# Projet_4A_Arrosage_Automatique1.net
KiCad netlist of a schematic drawn in EAGLE
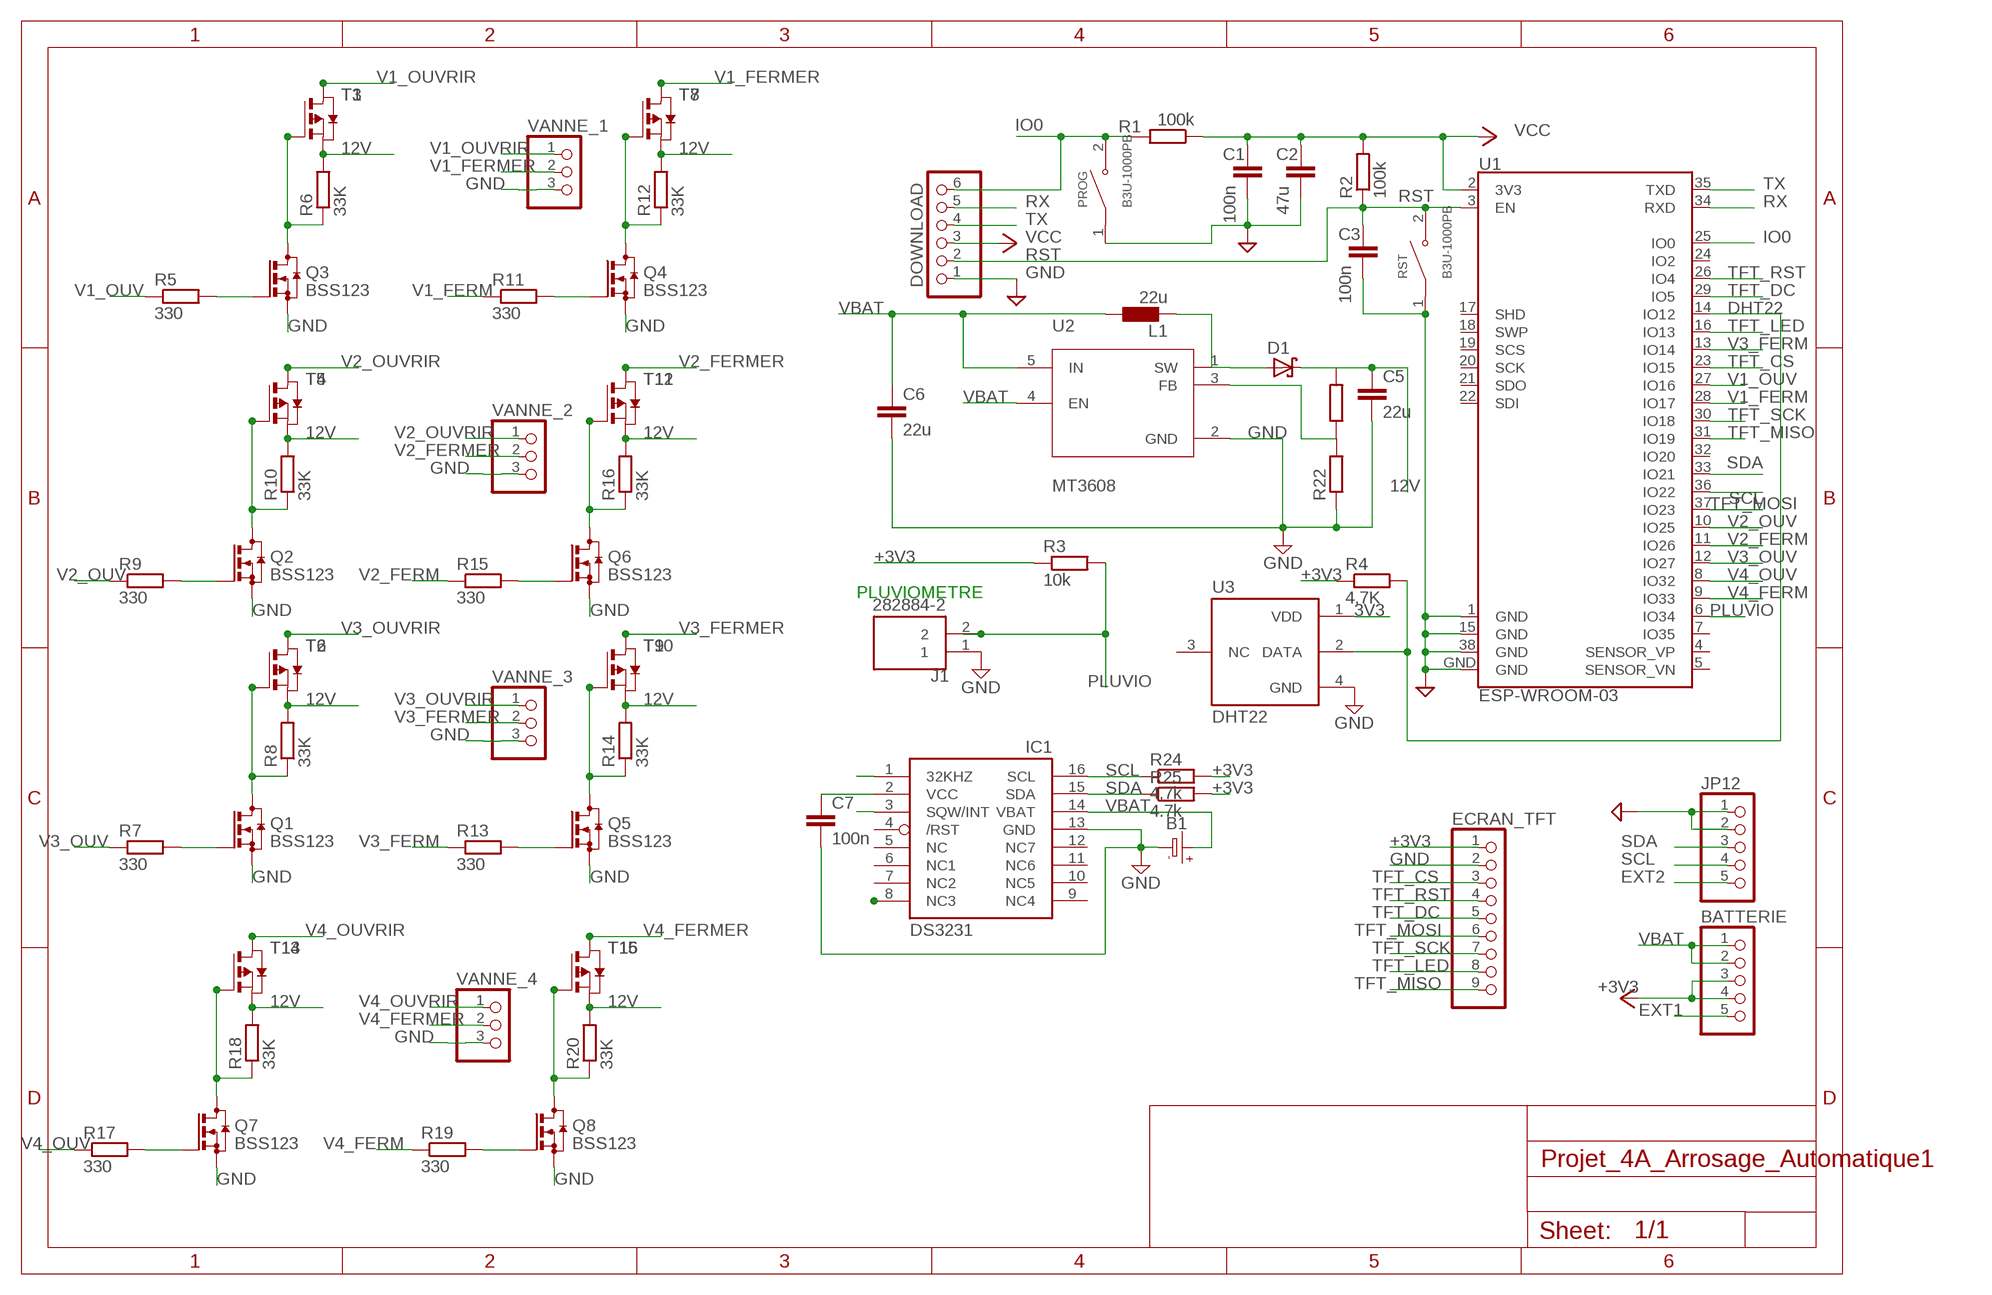
[diagram p0: schematic, sheet 1]

(export (version "E")
  (design (tool "Eeschema 10.0.6"))
  (components
    (comp (ref "B1")
      (value "BATTERYCR2032_BAT-HLD-001")
      (footprint "eagle-import:CR2032_SMT_BAT-HLD-001")
      (libsource (lib "eagle-import") (part "BATTERYCR2032_BAT-HLD-001"))
    )
    (comp (ref "BATTERIE")
      (value "PINHD-1X5S")
      (footprint "eagle-import:1X05S")
      (libsource (lib "eagle-import") (part "PINHD-1X5S"))
    )
    (comp (ref "C1")
      (value "100n")
      (footprint "eagle-import:C0805")
      (libsource (lib "eagle-import") (part "C"))
    )
    (comp (ref "C2")
      (value "47u")
      (footprint "eagle-import:C0805")
      (libsource (lib "eagle-import") (part "C"))
    )
    (comp (ref "C3")
      (value "100n")
      (footprint "eagle-import:C0805")
      (libsource (lib "eagle-import") (part "C"))
    )
    (comp (ref "C5")
      (value "22u")
      (footprint "eagle-import:C0805")
      (libsource (lib "eagle-import") (part "C"))
    )
    (comp (ref "C6")
      (value "22u")
      (footprint "eagle-import:C0805")
      (libsource (lib "eagle-import") (part "C"))
    )
    (comp (ref "C7")
      (value "100n")
      (footprint "eagle-import:C0805")
      (libsource (lib "eagle-import") (part "C"))
    )
    (comp (ref "D1")
      (value "SCHOTTKY-DIODEAG")
      (footprint "eagle-import:AG")
      (libsource (lib "eagle-import") (part "SCHOTTKY-DIODEAG"))
    )
    (comp (ref "DOWNLOAD")
      (value "PINHD-1X6S")
      (footprint "eagle-import:1X06S")
      (libsource (lib "eagle-import") (part "PINHD-1X6S"))
    )
    (comp (ref "ECRAN_TFT")
      (value "PINHD-1X9")
      (footprint "eagle-import:1X09")
      (libsource (lib "eagle-import") (part "PINHD-1X9"))
    )
    (comp (ref "IC1")
      (value "DS3231/SO")
      (footprint "eagle-import:SO16W")
      (fields (field (name "MF") "Analog Devices") (field (name "MP") "DS3231"))
      (libsource (lib "eagle-import") (part "DS3231/SO"))
    )
    (comp (ref "J1")
      (value "282884-2")
      (footprint "eagle-import:TE_282884-2")
      (fields (field (name "MF") "TE Connectivity"))
      (libsource (lib "eagle-import") (part "282884-2"))
    )
    (comp (ref "JP12")
      (value "PINHD-1X5S")
      (footprint "eagle-import:1X05S")
      (libsource (lib "eagle-import") (part "PINHD-1X5S"))
    )
    (comp (ref "L1")
      (value "22u")
      (footprint "eagle-import:0204_7")
      (libsource (lib "eagle-import") (part "L0204/7"))
    )
    (comp (ref "PROG")
      (value "B3U-1000PB")
      (footprint "eagle-import:SW_B3U-1000PB")
      (libsource (lib "eagle-import") (part "B3U-1000PB"))
    )
    (comp (ref "Q1")
      (value "BSS123")
      (footprint "eagle-import:SOT23")
      (libsource (lib "eagle-import") (part "BSS123"))
    )
    (comp (ref "Q2")
      (value "BSS123")
      (footprint "eagle-import:SOT23")
      (libsource (lib "eagle-import") (part "BSS123"))
    )
    (comp (ref "Q3")
      (value "BSS123")
      (footprint "eagle-import:SOT23")
      (libsource (lib "eagle-import") (part "BSS123"))
    )
    (comp (ref "Q4")
      (value "BSS123")
      (footprint "eagle-import:SOT23")
      (libsource (lib "eagle-import") (part "BSS123"))
    )
    (comp (ref "Q5")
      (value "BSS123")
      (footprint "eagle-import:SOT23")
      (libsource (lib "eagle-import") (part "BSS123"))
    )
    (comp (ref "Q6")
      (value "BSS123")
      (footprint "eagle-import:SOT23")
      (libsource (lib "eagle-import") (part "BSS123"))
    )
    (comp (ref "Q7")
      (value "BSS123")
      (footprint "eagle-import:SOT23")
      (libsource (lib "eagle-import") (part "BSS123"))
    )
    (comp (ref "Q8")
      (value "BSS123")
      (footprint "eagle-import:SOT23")
      (libsource (lib "eagle-import") (part "BSS123"))
    )
    (comp (ref "R1")
      (value "100k")
      (footprint "eagle-import:R1206")
      (libsource (lib "eagle-import") (part "RR1206"))
    )
    (comp (ref "R2")
      (value "100k")
      (footprint "eagle-import:R1206")
      (libsource (lib "eagle-import") (part "RR1206"))
    )
    (comp (ref "R3")
      (value "10k")
      (footprint "eagle-import:R0805")
      (libsource (lib "eagle-import") (part "R-EU_R0805"))
    )
    (comp (ref "R4")
      (value "4,7K")
      (footprint "eagle-import:0207_10")
      (libsource (lib "eagle-import") (part "R-EU_0207/10"))
    )
    (comp (ref "R5")
      (value "330")
      (footprint "eagle-import:0207_10")
      (libsource (lib "eagle-import") (part "R-EU_0207/10"))
    )
    (comp (ref "R6")
      (value "33K")
      (footprint "eagle-import:0207_10")
      (libsource (lib "eagle-import") (part "R-EU_0207/10"))
    )
    (comp (ref "R7")
      (value "330")
      (footprint "eagle-import:0207_10")
      (libsource (lib "eagle-import") (part "R-EU_0207/10"))
    )
    (comp (ref "R8")
      (value "33K")
      (footprint "eagle-import:0207_10")
      (libsource (lib "eagle-import") (part "R-EU_0207/10"))
    )
    (comp (ref "R9")
      (value "330")
      (footprint "eagle-import:0207_10")
      (libsource (lib "eagle-import") (part "R-EU_0207/10"))
    )
    (comp (ref "R10")
      (value "33K")
      (footprint "eagle-import:0207_10")
      (libsource (lib "eagle-import") (part "R-EU_0207/10"))
    )
    (comp (ref "R11")
      (value "330")
      (footprint "eagle-import:0207_10")
      (libsource (lib "eagle-import") (part "R-EU_0207/10"))
    )
    (comp (ref "R12")
      (value "33K")
      (footprint "eagle-import:0207_10")
      (libsource (lib "eagle-import") (part "R-EU_0207/10"))
    )
    (comp (ref "R13")
      (value "330")
      (footprint "eagle-import:0207_10")
      (libsource (lib "eagle-import") (part "R-EU_0207/10"))
    )
    (comp (ref "R14")
      (value "33K")
      (footprint "eagle-import:0207_10")
      (libsource (lib "eagle-import") (part "R-EU_0207/10"))
    )
    (comp (ref "R15")
      (value "330")
      (footprint "eagle-import:0207_10")
      (libsource (lib "eagle-import") (part "R-EU_0207/10"))
    )
    (comp (ref "R16")
      (value "33K")
      (footprint "eagle-import:0207_10")
      (libsource (lib "eagle-import") (part "R-EU_0207/10"))
    )
    (comp (ref "R17")
      (value "330")
      (footprint "eagle-import:0207_10")
      (libsource (lib "eagle-import") (part "R-EU_0207/10"))
    )
    (comp (ref "R18")
      (value "33K")
      (footprint "eagle-import:0207_10")
      (libsource (lib "eagle-import") (part "R-EU_0207/10"))
    )
    (comp (ref "R19")
      (value "330")
      (footprint "eagle-import:0207_10")
      (libsource (lib "eagle-import") (part "R-EU_0207/10"))
    )
    (comp (ref "R20")
      (value "33K")
      (footprint "eagle-import:0207_10")
      (libsource (lib "eagle-import") (part "R-EU_0207/10"))
    )
    (comp (ref "R22")
      (value "R-EU_0204/2V")
      (footprint "eagle-import:0204V")
      (libsource (lib "eagle-import") (part "R-EU_0204/2V"))
    )
    (comp (ref "R24")
      (value "4,7k")
      (footprint "eagle-import:0204V")
      (libsource (lib "eagle-import") (part "R-EU_0204/2V"))
    )
    (comp (ref "R25")
      (value "4.7k")
      (footprint "eagle-import:0204V")
      (libsource (lib "eagle-import") (part "R-EU_0204/2V"))
    )
    (comp (ref "RST")
      (value "B3U-1000PB")
      (footprint "eagle-import:SW_B3U-1000PB")
      (libsource (lib "eagle-import") (part "B3U-1000PB"))
    )
    (comp (ref "T1")
      (value "PMOSSOT23")
      (footprint "eagle-import:SOT-23")
      (libsource (lib "eagle-import") (part "PMOSSOT23"))
    )
    (comp (ref "T2")
      (value "PMOSSOT23")
      (footprint "eagle-import:SOT-23")
      (libsource (lib "eagle-import") (part "PMOSSOT23"))
    )
    (comp (ref "T3")
      (value "PMOSSOT23")
      (footprint "eagle-import:SOT-23")
      (libsource (lib "eagle-import") (part "PMOSSOT23"))
    )
    (comp (ref "T4")
      (value "PMOSSOT23")
      (footprint "eagle-import:SOT-23")
      (libsource (lib "eagle-import") (part "PMOSSOT23"))
    )
    (comp (ref "T5")
      (value "PMOSSOT23")
      (footprint "eagle-import:SOT-23")
      (libsource (lib "eagle-import") (part "PMOSSOT23"))
    )
    (comp (ref "T6")
      (value "PMOSSOT23")
      (footprint "eagle-import:SOT-23")
      (libsource (lib "eagle-import") (part "PMOSSOT23"))
    )
    (comp (ref "T7")
      (value "PMOSSOT23")
      (footprint "eagle-import:SOT-23")
      (libsource (lib "eagle-import") (part "PMOSSOT23"))
    )
    (comp (ref "T8")
      (value "PMOSSOT23")
      (footprint "eagle-import:SOT-23")
      (libsource (lib "eagle-import") (part "PMOSSOT23"))
    )
    (comp (ref "T9")
      (value "PMOSSOT23")
      (footprint "eagle-import:SOT-23")
      (libsource (lib "eagle-import") (part "PMOSSOT23"))
    )
    (comp (ref "T10")
      (value "PMOSSOT23")
      (footprint "eagle-import:SOT-23")
      (libsource (lib "eagle-import") (part "PMOSSOT23"))
    )
    (comp (ref "T11")
      (value "PMOSSOT23")
      (footprint "eagle-import:SOT-23")
      (libsource (lib "eagle-import") (part "PMOSSOT23"))
    )
    (comp (ref "T12")
      (value "PMOSSOT23")
      (footprint "eagle-import:SOT-23")
      (libsource (lib "eagle-import") (part "PMOSSOT23"))
    )
    (comp (ref "T13")
      (value "PMOSSOT23")
      (footprint "eagle-import:SOT-23")
      (libsource (lib "eagle-import") (part "PMOSSOT23"))
    )
    (comp (ref "T14")
      (value "PMOSSOT23")
      (footprint "eagle-import:SOT-23")
      (libsource (lib "eagle-import") (part "PMOSSOT23"))
    )
    (comp (ref "T15")
      (value "PMOSSOT23")
      (footprint "eagle-import:SOT-23")
      (libsource (lib "eagle-import") (part "PMOSSOT23"))
    )
    (comp (ref "T16")
      (value "PMOSSOT23")
      (footprint "eagle-import:SOT-23")
      (libsource (lib "eagle-import") (part "PMOSSOT23"))
    )
    (comp (ref "U1")
      (value "ESP-WROOM-03")
      (footprint "eagle-import:ESP-WROOM-03")
      (libsource (lib "eagle-import") (part "ESP-WROOM-03"))
    )
    (comp (ref "U2")
      (value "MT3608")
      (footprint "eagle-import:SOT95P280X145-6N")
      (fields (field (name "MANUFACTURER") "Aero Semi"))
      (libsource (lib "eagle-import") (part "MT3608"))
    )
    (comp (ref "U3")
      (value "DHT22")
      (footprint "eagle-import:XDCR_DHT22")
      (fields (field (name "MF") "Aosong Electronics"))
      (libsource (lib "eagle-import") (part "DHT22"))
    )
    (comp (ref "VANNE_1")
      (value "PINHD-1X3")
      (footprint "eagle-import:1X03")
      (libsource (lib "eagle-import") (part "PINHD-1X3"))
    )
    (comp (ref "VANNE_2")
      (value "PINHD-1X3")
      (footprint "eagle-import:1X03")
      (libsource (lib "eagle-import") (part "PINHD-1X3"))
    )
    (comp (ref "VANNE_3")
      (value "PINHD-1X3")
      (footprint "eagle-import:1X03")
      (libsource (lib "eagle-import") (part "PINHD-1X3"))
    )
    (comp (ref "VANNE_4")
      (value "PINHD-1X3")
      (footprint "eagle-import:1X03")
      (libsource (lib "eagle-import") (part "PINHD-1X3"))
    )
  )
  (nets
    (net (code "1") (name "+3V3") (class "Default")
      (node (ref "BATTERIE") (pin "3") (pinfunction "3_3") (pintype "passive"))
      (node (ref "BATTERIE") (pin "4") (pinfunction "4_4") (pintype "passive"))
      (node (ref "C7") (pin "1") (pinfunction "1_1") (pintype "passive"))
      (node (ref "ECRAN_TFT") (pin "1") (pinfunction "1_1") (pintype "passive"))
      (node (ref "IC1") (pin "2") (pinfunction "VCC_2") (pintype "power_in"))
      (node (ref "R24") (pin "2") (pinfunction "2_2") (pintype "passive"))
      (node (ref "R25") (pin "2") (pinfunction "2_2") (pintype "passive"))
      (node (ref "R3") (pin "1") (pinfunction "1_1") (pintype "passive"))
      (node (ref "R4") (pin "1") (pinfunction "1_1") (pintype "passive"))
    )
    (net (code "2") (name "/3V3") (class "Default")
      (node (ref "U3") (pin "1") (pinfunction "VDD_1") (pintype "power_in"))
    )
    (net (code "3") (name "/12V") (class "Default")
      (node (ref "C5") (pin "1") (pinfunction "1_1") (pintype "passive"))
      (node (ref "D1") (pin "C") (pinfunction "C_C") (pintype "passive"))
      (node (ref "R10") (pin "2") (pinfunction "2_2") (pintype "passive"))
      (node (ref "R12") (pin "2") (pinfunction "2_2") (pintype "passive"))
      (node (ref "R14") (pin "2") (pinfunction "2_2") (pintype "passive"))
      (node (ref "R16") (pin "2") (pinfunction "2_2") (pintype "passive"))
      (node (ref "R18") (pin "2") (pinfunction "2_2") (pintype "passive"))
      (node (ref "R20") (pin "2") (pinfunction "2_2") (pintype "passive"))
      (node (ref "R6") (pin "2") (pinfunction "2_2") (pintype "passive"))
      (node (ref "R8") (pin "2") (pinfunction "2_2") (pintype "passive"))
      (node (ref "T1") (pin "2") (pinfunction "S_2") (pintype "passive"))
      (node (ref "T10") (pin "2") (pinfunction "S_2") (pintype "passive"))
      (node (ref "T11") (pin "2") (pinfunction "S_2") (pintype "passive"))
      (node (ref "T12") (pin "2") (pinfunction "S_2") (pintype "passive"))
      (node (ref "T13") (pin "2") (pinfunction "S_2") (pintype "passive"))
      (node (ref "T14") (pin "2") (pinfunction "S_2") (pintype "passive"))
      (node (ref "T15") (pin "2") (pinfunction "S_2") (pintype "passive"))
      (node (ref "T16") (pin "2") (pinfunction "S_2") (pintype "passive"))
      (node (ref "T2") (pin "2") (pinfunction "S_2") (pintype "passive"))
      (node (ref "T3") (pin "2") (pinfunction "S_2") (pintype "passive"))
      (node (ref "T4") (pin "2") (pinfunction "S_2") (pintype "passive"))
      (node (ref "T5") (pin "2") (pinfunction "S_2") (pintype "passive"))
      (node (ref "T6") (pin "2") (pinfunction "S_2") (pintype "passive"))
      (node (ref "T7") (pin "2") (pinfunction "S_2") (pintype "passive"))
      (node (ref "T8") (pin "2") (pinfunction "S_2") (pintype "passive"))
      (node (ref "T9") (pin "2") (pinfunction "S_2") (pintype "passive"))
    )
    (net (code "4") (name "/DHT22") (class "Default")
      (node (ref "R4") (pin "2") (pinfunction "2_2") (pintype "passive"))
      (node (ref "U1") (pin "14") (pinfunction "IO12_14") (pintype "bidirectional"))
      (node (ref "U3") (pin "2") (pinfunction "DATA_2") (pintype "bidirectional"))
    )
    (net (code "5") (name "/EXT1") (class "Default")
      (node (ref "BATTERIE") (pin "5") (pinfunction "5_5") (pintype "passive"))
    )
    (net (code "6") (name "/EXT2") (class "Default")
      (node (ref "JP12") (pin "5") (pinfunction "5_5") (pintype "passive"))
    )
    (net (code "7") (name "/IO0") (class "Default")
      (node (ref "DOWNLOAD") (pin "6") (pinfunction "6_6") (pintype "passive"))
      (node (ref "PROG") (pin "2") (pinfunction "2_2") (pintype "passive"))
      (node (ref "R1") (pin "2") (pinfunction "2_2") (pintype "passive"))
      (node (ref "U1") (pin "25") (pinfunction "IO0_25") (pintype "bidirectional"))
    )
    (net (code "8") (name "/PLUVIO") (class "Default")
      (node (ref "J1") (pin "2") (pinfunction "2_2") (pintype "passive"))
      (node (ref "R3") (pin "2") (pinfunction "2_2") (pintype "passive"))
      (node (ref "U1") (pin "6") (pinfunction "IO34_6") (pintype "bidirectional"))
    )
    (net (code "9") (name "/RST") (class "Default")
      (node (ref "C3") (pin "1") (pinfunction "1_1") (pintype "passive"))
      (node (ref "DOWNLOAD") (pin "2") (pinfunction "2_2") (pintype "passive"))
      (node (ref "R2") (pin "1") (pinfunction "1_1") (pintype "passive"))
      (node (ref "RST") (pin "2") (pinfunction "2_2") (pintype "passive"))
      (node (ref "U1") (pin "3") (pinfunction "EN_3") (pintype "bidirectional"))
    )
    (net (code "10") (name "/RX") (class "Default")
      (node (ref "DOWNLOAD") (pin "5") (pinfunction "5_5") (pintype "passive"))
      (node (ref "U1") (pin "34") (pinfunction "RXD_34") (pintype "bidirectional"))
    )
    (net (code "11") (name "/SCL") (class "Default")
      (node (ref "IC1") (pin "16") (pinfunction "SCL_16") (pintype "bidirectional"))
      (node (ref "JP12") (pin "4") (pinfunction "4_4") (pintype "passive"))
      (node (ref "R24") (pin "1") (pinfunction "1_1") (pintype "passive"))
      (node (ref "U1") (pin "36") (pinfunction "IO22_36") (pintype "bidirectional"))
    )
    (net (code "12") (name "/SDA") (class "Default")
      (node (ref "IC1") (pin "15") (pinfunction "SDA_15") (pintype "bidirectional"))
      (node (ref "JP12") (pin "3") (pinfunction "3_3") (pintype "passive"))
      (node (ref "R25") (pin "1") (pinfunction "1_1") (pintype "passive"))
      (node (ref "U1") (pin "33") (pinfunction "IO21_33") (pintype "bidirectional"))
    )
    (net (code "13") (name "/TFT_CS") (class "Default")
      (node (ref "ECRAN_TFT") (pin "3") (pinfunction "3_3") (pintype "passive"))
      (node (ref "U1") (pin "23") (pinfunction "IO15_23") (pintype "bidirectional"))
    )
    (net (code "14") (name "/TFT_DC") (class "Default")
      (node (ref "ECRAN_TFT") (pin "5") (pinfunction "5_5") (pintype "passive"))
      (node (ref "U1") (pin "29") (pinfunction "IO5_29") (pintype "bidirectional"))
    )
    (net (code "15") (name "/TFT_LED") (class "Default")
      (node (ref "ECRAN_TFT") (pin "8") (pinfunction "8_8") (pintype "passive"))
      (node (ref "U1") (pin "16") (pinfunction "IO13_16") (pintype "bidirectional"))
    )
    (net (code "16") (name "/TFT_MISO") (class "Default")
      (node (ref "ECRAN_TFT") (pin "9") (pinfunction "9_9") (pintype "passive"))
      (node (ref "U1") (pin "31") (pinfunction "IO19_31") (pintype "bidirectional"))
    )
    (net (code "17") (name "/TFT_MOSI") (class "Default")
      (node (ref "ECRAN_TFT") (pin "6") (pinfunction "6_6") (pintype "passive"))
      (node (ref "U1") (pin "37") (pinfunction "IO23_37") (pintype "bidirectional"))
    )
    (net (code "18") (name "/TFT_RST") (class "Default")
      (node (ref "ECRAN_TFT") (pin "4") (pinfunction "4_4") (pintype "passive"))
      (node (ref "U1") (pin "26") (pinfunction "IO4_26") (pintype "bidirectional"))
    )
    (net (code "19") (name "/TFT_SCK") (class "Default")
      (node (ref "ECRAN_TFT") (pin "7") (pinfunction "7_7") (pintype "passive"))
      (node (ref "U1") (pin "30") (pinfunction "IO18_30") (pintype "bidirectional"))
    )
    (net (code "20") (name "/TX") (class "Default")
      (node (ref "DOWNLOAD") (pin "4") (pinfunction "4_4") (pintype "passive"))
      (node (ref "U1") (pin "35") (pinfunction "TXD_35") (pintype "bidirectional"))
    )
    (net (code "21") (name "/V1_FERM") (class "Default")
      (node (ref "R11") (pin "1") (pinfunction "1_1") (pintype "passive"))
      (node (ref "U1") (pin "28") (pinfunction "IO17_28") (pintype "bidirectional"))
    )
    (net (code "22") (name "/V1_FERMER") (class "Default")
      (node (ref "T7") (pin "1") (pinfunction "D_1") (pintype "passive"))
      (node (ref "T8") (pin "1") (pinfunction "D_1") (pintype "passive"))
      (node (ref "VANNE_1") (pin "2") (pinfunction "2_2") (pintype "passive"))
    )
    (net (code "23") (name "/V1_OUV") (class "Default")
      (node (ref "R5") (pin "1") (pinfunction "1_1") (pintype "passive"))
      (node (ref "U1") (pin "27") (pinfunction "IO16_27") (pintype "bidirectional"))
    )
    (net (code "24") (name "/V1_OUVRIR") (class "Default")
      (node (ref "T1") (pin "1") (pinfunction "D_1") (pintype "passive"))
      (node (ref "T3") (pin "1") (pinfunction "D_1") (pintype "passive"))
      (node (ref "VANNE_1") (pin "1") (pinfunction "1_1") (pintype "passive"))
    )
    (net (code "25") (name "/V2_FERM") (class "Default")
      (node (ref "R15") (pin "1") (pinfunction "1_1") (pintype "passive"))
      (node (ref "U1") (pin "11") (pinfunction "IO26_11") (pintype "bidirectional"))
    )
    (net (code "26") (name "/V2_FERMER") (class "Default")
      (node (ref "T11") (pin "1") (pinfunction "D_1") (pintype "passive"))
      (node (ref "T12") (pin "1") (pinfunction "D_1") (pintype "passive"))
      (node (ref "VANNE_2") (pin "2") (pinfunction "2_2") (pintype "passive"))
    )
    (net (code "27") (name "/V2_OUV") (class "Default")
      (node (ref "R9") (pin "1") (pinfunction "1_1") (pintype "passive"))
      (node (ref "U1") (pin "10") (pinfunction "IO25_10") (pintype "bidirectional"))
    )
    (net (code "28") (name "/V2_OUVRIR") (class "Default")
      (node (ref "T4") (pin "1") (pinfunction "D_1") (pintype "passive"))
      (node (ref "T5") (pin "1") (pinfunction "D_1") (pintype "passive"))
      (node (ref "VANNE_2") (pin "1") (pinfunction "1_1") (pintype "passive"))
    )
    (net (code "29") (name "/V3_FERM") (class "Default")
      (node (ref "R13") (pin "1") (pinfunction "1_1") (pintype "passive"))
      (node (ref "U1") (pin "13") (pinfunction "IO14_13") (pintype "bidirectional"))
    )
    (net (code "30") (name "/V3_FERMER") (class "Default")
      (node (ref "T10") (pin "1") (pinfunction "D_1") (pintype "passive"))
      (node (ref "T9") (pin "1") (pinfunction "D_1") (pintype "passive"))
      (node (ref "VANNE_3") (pin "2") (pinfunction "2_2") (pintype "passive"))
    )
    (net (code "31") (name "/V3_OUV") (class "Default")
      (node (ref "R7") (pin "1") (pinfunction "1_1") (pintype "passive"))
      (node (ref "U1") (pin "12") (pinfunction "IO27_12") (pintype "bidirectional"))
    )
    (net (code "32") (name "/V3_OUVRIR") (class "Default")
      (node (ref "T2") (pin "1") (pinfunction "D_1") (pintype "passive"))
      (node (ref "T6") (pin "1") (pinfunction "D_1") (pintype "passive"))
      (node (ref "VANNE_3") (pin "1") (pinfunction "1_1") (pintype "passive"))
    )
    (net (code "33") (name "/V4_FERM") (class "Default")
      (node (ref "R19") (pin "1") (pinfunction "1_1") (pintype "passive"))
      (node (ref "U1") (pin "9") (pinfunction "IO33_9") (pintype "bidirectional"))
    )
    (net (code "34") (name "/V4_FERMER") (class "Default")
      (node (ref "T15") (pin "1") (pinfunction "D_1") (pintype "passive"))
      (node (ref "T16") (pin "1") (pinfunction "D_1") (pintype "passive"))
      (node (ref "VANNE_4") (pin "2") (pinfunction "2_2") (pintype "passive"))
    )
    (net (code "35") (name "/V4_OUV") (class "Default")
      (node (ref "R17") (pin "1") (pinfunction "1_1") (pintype "passive"))
      (node (ref "U1") (pin "8") (pinfunction "IO32_8") (pintype "bidirectional"))
    )
    (net (code "36") (name "/V4_OUVRIR") (class "Default")
      (node (ref "T13") (pin "1") (pinfunction "D_1") (pintype "passive"))
      (node (ref "T14") (pin "1") (pinfunction "D_1") (pintype "passive"))
      (node (ref "VANNE_4") (pin "1") (pinfunction "1_1") (pintype "passive"))
    )
    (net (code "37") (name "/VBAT") (class "Default")
      (node (ref "B1") (pin "+$1") (pinfunction "+_+$1") (pintype "passive"))
      (node (ref "B1") (pin "+$2") (pinfunction "+_+$2") (pintype "passive"))
      (node (ref "BATTERIE") (pin "1") (pinfunction "1_1") (pintype "passive"))
      (node (ref "BATTERIE") (pin "2") (pinfunction "2_2") (pintype "passive"))
      (node (ref "C6") (pin "1") (pinfunction "1_1") (pintype "passive"))
      (node (ref "IC1") (pin "14") (pinfunction "VBAT_14") (pintype "power_in"))
      (node (ref "L1") (pin "1") (pinfunction "1_1") (pintype "passive"))
      (node (ref "U2") (pin "4") (pinfunction "EN_4") (pintype "input"))
      (node (ref "U2") (pin "5") (pinfunction "IN_5") (pintype "input"))
    )
    (net (code "38") (name "GND") (class "Default")
      (node (ref "B1") (pin "-") (pinfunction "-_-") (pintype "passive"))
      (node (ref "C1") (pin "2") (pinfunction "2_2") (pintype "passive"))
      (node (ref "C2") (pin "2") (pinfunction "2_2") (pintype "passive"))
      (node (ref "C3") (pin "2") (pinfunction "2_2") (pintype "passive"))
      (node (ref "C5") (pin "2") (pinfunction "2_2") (pintype "passive"))
      (node (ref "C6") (pin "2") (pinfunction "2_2") (pintype "passive"))
      (node (ref "C7") (pin "2") (pinfunction "2_2") (pintype "passive"))
      (node (ref "DOWNLOAD") (pin "1") (pinfunction "1_1") (pintype "passive"))
      (node (ref "ECRAN_TFT") (pin "2") (pinfunction "2_2") (pintype "passive"))
      (node (ref "IC1") (pin "13") (pinfunction "GND_13") (pintype "power_in"))
      (node (ref "J1") (pin "1") (pinfunction "1_1") (pintype "passive"))
      (node (ref "JP12") (pin "1") (pinfunction "1_1") (pintype "passive"))
      (node (ref "JP12") (pin "2") (pinfunction "2_2") (pintype "passive"))
      (node (ref "PROG") (pin "1") (pinfunction "1_1") (pintype "passive"))
      (node (ref "Q1") (pin "2") (pinfunction "S_2") (pintype "passive"))
      (node (ref "Q2") (pin "2") (pinfunction "S_2") (pintype "passive"))
      (node (ref "Q3") (pin "2") (pinfunction "S_2") (pintype "passive"))
      (node (ref "Q4") (pin "2") (pinfunction "S_2") (pintype "passive"))
      (node (ref "Q5") (pin "2") (pinfunction "S_2") (pintype "passive"))
      (node (ref "Q6") (pin "2") (pinfunction "S_2") (pintype "passive"))
      (node (ref "Q7") (pin "2") (pinfunction "S_2") (pintype "passive"))
      (node (ref "Q8") (pin "2") (pinfunction "S_2") (pintype "passive"))
      (node (ref "R22") (pin "1") (pinfunction "1_1") (pintype "passive"))
      (node (ref "RST") (pin "1") (pinfunction "1_1") (pintype "passive"))
      (node (ref "U1") (pin "1") (pinfunction "GND_1") (pintype "bidirectional"))
      (node (ref "U1") (pin "15") (pinfunction "GND_15") (pintype "bidirectional"))
      (node (ref "U1") (pin "38") (pinfunction "GND_38") (pintype "bidirectional"))
      (node (ref "U1") (pin "GND") (pinfunction "GND_GND") (pintype "bidirectional"))
      (node (ref "U2") (pin "2") (pinfunction "GND_2") (pintype "power_in"))
      (node (ref "U3") (pin "4") (pinfunction "GND_4") (pintype "power_in"))
      (node (ref "VANNE_1") (pin "3") (pinfunction "3_3") (pintype "passive"))
      (node (ref "VANNE_2") (pin "3") (pinfunction "3_3") (pintype "passive"))
      (node (ref "VANNE_3") (pin "3") (pinfunction "3_3") (pintype "passive"))
      (node (ref "VANNE_4") (pin "3") (pinfunction "3_3") (pintype "passive"))
    )
    (net (code "39") (name "Net-(Q1-D)") (class "Default")
      (node (ref "Q1") (pin "3") (pinfunction "D_3") (pintype "passive"))
      (node (ref "R8") (pin "1") (pinfunction "1_1") (pintype "passive"))
      (node (ref "T2") (pin "3") (pinfunction "G_3") (pintype "passive"))
      (node (ref "T6") (pin "3") (pinfunction "G_3") (pintype "passive"))
    )
    (net (code "40") (name "Net-(Q1-G)") (class "Default")
      (node (ref "Q1") (pin "1") (pinfunction "G_1") (pintype "passive"))
      (node (ref "R7") (pin "2") (pinfunction "2_2") (pintype "passive"))
    )
    (net (code "41") (name "Net-(Q2-D)") (class "Default")
      (node (ref "Q2") (pin "3") (pinfunction "D_3") (pintype "passive"))
      (node (ref "R10") (pin "1") (pinfunction "1_1") (pintype "passive"))
      (node (ref "T4") (pin "3") (pinfunction "G_3") (pintype "passive"))
      (node (ref "T5") (pin "3") (pinfunction "G_3") (pintype "passive"))
    )
    (net (code "42") (name "Net-(Q2-G)") (class "Default")
      (node (ref "Q2") (pin "1") (pinfunction "G_1") (pintype "passive"))
      (node (ref "R9") (pin "2") (pinfunction "2_2") (pintype "passive"))
    )
    (net (code "43") (name "Net-(Q3-D)") (class "Default")
      (node (ref "Q3") (pin "3") (pinfunction "D_3") (pintype "passive"))
      (node (ref "R6") (pin "1") (pinfunction "1_1") (pintype "passive"))
      (node (ref "T1") (pin "3") (pinfunction "G_3") (pintype "passive"))
      (node (ref "T3") (pin "3") (pinfunction "G_3") (pintype "passive"))
    )
    (net (code "44") (name "Net-(Q3-G)") (class "Default")
      (node (ref "Q3") (pin "1") (pinfunction "G_1") (pintype "passive"))
      (node (ref "R5") (pin "2") (pinfunction "2_2") (pintype "passive"))
    )
    (net (code "45") (name "Net-(Q4-D)") (class "Default")
      (node (ref "Q4") (pin "3") (pinfunction "D_3") (pintype "passive"))
      (node (ref "R12") (pin "1") (pinfunction "1_1") (pintype "passive"))
      (node (ref "T7") (pin "3") (pinfunction "G_3") (pintype "passive"))
      (node (ref "T8") (pin "3") (pinfunction "G_3") (pintype "passive"))
    )
    (net (code "46") (name "Net-(Q4-G)") (class "Default")
      (node (ref "Q4") (pin "1") (pinfunction "G_1") (pintype "passive"))
      (node (ref "R11") (pin "2") (pinfunction "2_2") (pintype "passive"))
    )
    (net (code "47") (name "Net-(Q5-D)") (class "Default")
      (node (ref "Q5") (pin "3") (pinfunction "D_3") (pintype "passive"))
      (node (ref "R14") (pin "1") (pinfunction "1_1") (pintype "passive"))
      (node (ref "T10") (pin "3") (pinfunction "G_3") (pintype "passive"))
      (node (ref "T9") (pin "3") (pinfunction "G_3") (pintype "passive"))
    )
    (net (code "48") (name "Net-(Q5-G)") (class "Default")
      (node (ref "Q5") (pin "1") (pinfunction "G_1") (pintype "passive"))
      (node (ref "R13") (pin "2") (pinfunction "2_2") (pintype "passive"))
    )
    (net (code "49") (name "Net-(Q6-D)") (class "Default")
      (node (ref "Q6") (pin "3") (pinfunction "D_3") (pintype "passive"))
      (node (ref "R16") (pin "1") (pinfunction "1_1") (pintype "passive"))
      (node (ref "T11") (pin "3") (pinfunction "G_3") (pintype "passive"))
      (node (ref "T12") (pin "3") (pinfunction "G_3") (pintype "passive"))
    )
    (net (code "50") (name "Net-(Q6-G)") (class "Default")
      (node (ref "Q6") (pin "1") (pinfunction "G_1") (pintype "passive"))
      (node (ref "R15") (pin "2") (pinfunction "2_2") (pintype "passive"))
    )
    (net (code "51") (name "Net-(Q7-D)") (class "Default")
      (node (ref "Q7") (pin "3") (pinfunction "D_3") (pintype "passive"))
      (node (ref "R18") (pin "1") (pinfunction "1_1") (pintype "passive"))
      (node (ref "T13") (pin "3") (pinfunction "G_3") (pintype "passive"))
      (node (ref "T14") (pin "3") (pinfunction "G_3") (pintype "passive"))
    )
    (net (code "52") (name "Net-(Q7-G)") (class "Default")
      (node (ref "Q7") (pin "1") (pinfunction "G_1") (pintype "passive"))
      (node (ref "R17") (pin "2") (pinfunction "2_2") (pintype "passive"))
    )
    (net (code "53") (name "Net-(Q8-D)") (class "Default")
      (node (ref "Q8") (pin "3") (pinfunction "D_3") (pintype "passive"))
      (node (ref "R20") (pin "1") (pinfunction "1_1") (pintype "passive"))
      (node (ref "T15") (pin "3") (pinfunction "G_3") (pintype "passive"))
      (node (ref "T16") (pin "3") (pinfunction "G_3") (pintype "passive"))
    )
    (net (code "54") (name "Net-(Q8-G)") (class "Default")
      (node (ref "Q8") (pin "1") (pinfunction "G_1") (pintype "passive"))
      (node (ref "R19") (pin "2") (pinfunction "2_2") (pintype "passive"))
    )
    (net (code "55") (name "Net-(U2-FB)") (class "Default")
      (node (ref "R22") (pin "2") (pinfunction "2_2") (pintype "passive"))
      (node (ref "U2") (pin "3") (pinfunction "FB_3") (pintype "input"))
    )
    (net (code "56") (name "Net-(U2-SW)") (class "Default")
      (node (ref "D1") (pin "A") (pinfunction "A_A") (pintype "passive"))
      (node (ref "L1") (pin "2") (pinfunction "2_2") (pintype "passive"))
      (node (ref "U2") (pin "1") (pinfunction "SW_1") (pintype "output"))
    )
    (net (code "57") (name "VCC") (class "Default")
      (node (ref "C1") (pin "1") (pinfunction "1_1") (pintype "passive"))
      (node (ref "C2") (pin "1") (pinfunction "1_1") (pintype "passive"))
      (node (ref "DOWNLOAD") (pin "3") (pinfunction "3_3") (pintype "passive"))
      (node (ref "R1") (pin "1") (pinfunction "1_1") (pintype "passive"))
      (node (ref "R2") (pin "2") (pinfunction "2_2") (pintype "passive"))
      (node (ref "U1") (pin "2") (pinfunction "3V3_2") (pintype "bidirectional"))
    )
    (net (code "58") (name "unconnected-(IC1-32KHZ-Pad1)") (class "Default")
      (node (ref "IC1") (pin "1") (pinfunction "32KHZ_1") (pintype "output"))
    )
    (net (code "59") (name "unconnected-(IC1-NC-Pad5)") (class "Default")
      (node (ref "IC1") (pin "5") (pinfunction "NC_5") (pintype "no_connect"))
    )
    (net (code "60") (name "unconnected-(IC1-NC1-Pad6)") (class "Default")
      (node (ref "IC1") (pin "6") (pinfunction "NC1_6") (pintype "no_connect"))
    )
    (net (code "61") (name "unconnected-(IC1-NC2-Pad7)") (class "Default")
      (node (ref "IC1") (pin "7") (pinfunction "NC2_7") (pintype "no_connect"))
    )
    (net (code "62") (name "unconnected-(IC1-NC3-Pad8)") (class "Default")
      (node (ref "IC1") (pin "8") (pinfunction "NC3_8") (pintype "no_connect"))
    )
    (net (code "63") (name "unconnected-(IC1-NC4-Pad9)") (class "Default")
      (node (ref "IC1") (pin "9") (pinfunction "NC4_9") (pintype "no_connect"))
    )
    (net (code "64") (name "unconnected-(IC1-NC5-Pad10)") (class "Default")
      (node (ref "IC1") (pin "10") (pinfunction "NC5_10") (pintype "no_connect"))
    )
    (net (code "65") (name "unconnected-(IC1-NC6-Pad11)") (class "Default")
      (node (ref "IC1") (pin "11") (pinfunction "NC6_11") (pintype "no_connect"))
    )
    (net (code "66") (name "unconnected-(IC1-NC7-Pad12)") (class "Default")
      (node (ref "IC1") (pin "12") (pinfunction "NC7_12") (pintype "no_connect"))
    )
    (net (code "67") (name "unconnected-(IC1-SQW{slash}INT-Pad3)") (class "Default")
      (node (ref "IC1") (pin "3") (pinfunction "SQW/INT_3") (pintype "output"))
    )
    (net (code "68") (name "unconnected-(IC1-{slash}RST-Pad4)") (class "Default")
      (node (ref "IC1") (pin "4") (pinfunction "/RST_4") (pintype "passive"))
    )
    (net (code "69") (name "unconnected-(U1-IO2-Pad24)") (class "Default")
      (node (ref "U1") (pin "24") (pinfunction "IO2_24") (pintype "bidirectional"))
    )
    (net (code "70") (name "unconnected-(U1-IO20-Pad32)") (class "Default")
      (node (ref "U1") (pin "32") (pinfunction "IO20_32") (pintype "bidirectional"))
    )
    (net (code "71") (name "unconnected-(U1-IO35-Pad7)") (class "Default")
      (node (ref "U1") (pin "7") (pinfunction "IO35_7") (pintype "bidirectional"))
    )
    (net (code "72") (name "unconnected-(U1-SCK-Pad20)") (class "Default")
      (node (ref "U1") (pin "20") (pinfunction "SCK_20") (pintype "bidirectional"))
    )
    (net (code "73") (name "unconnected-(U1-SCS-Pad19)") (class "Default")
      (node (ref "U1") (pin "19") (pinfunction "SCS_19") (pintype "bidirectional"))
    )
    (net (code "74") (name "unconnected-(U1-SDI-Pad22)") (class "Default")
      (node (ref "U1") (pin "22") (pinfunction "SDI_22") (pintype "bidirectional"))
    )
    (net (code "75") (name "unconnected-(U1-SDO-Pad21)") (class "Default")
      (node (ref "U1") (pin "21") (pinfunction "SDO_21") (pintype "bidirectional"))
    )
    (net (code "76") (name "unconnected-(U1-SENSOR_VN-Pad5)") (class "Default")
      (node (ref "U1") (pin "5") (pinfunction "SENSOR_VN_5") (pintype "bidirectional"))
    )
    (net (code "77") (name "unconnected-(U1-SENSOR_VP-Pad4)") (class "Default")
      (node (ref "U1") (pin "4") (pinfunction "SENSOR_VP_4") (pintype "bidirectional"))
    )
    (net (code "78") (name "unconnected-(U1-SHD-Pad17)") (class "Default")
      (node (ref "U1") (pin "17") (pinfunction "SHD_17") (pintype "bidirectional"))
    )
    (net (code "79") (name "unconnected-(U1-SWP-Pad18)") (class "Default")
      (node (ref "U1") (pin "18") (pinfunction "SWP_18") (pintype "bidirectional"))
    )
    (net (code "80") (name "unconnected-(U3-NC-Pad3)") (class "Default")
      (node (ref "U3") (pin "3") (pinfunction "NC_3") (pintype "no_connect"))
    )
  )
)
